# -.net
KiCad netlist of a schematic drawn in Altium Designer
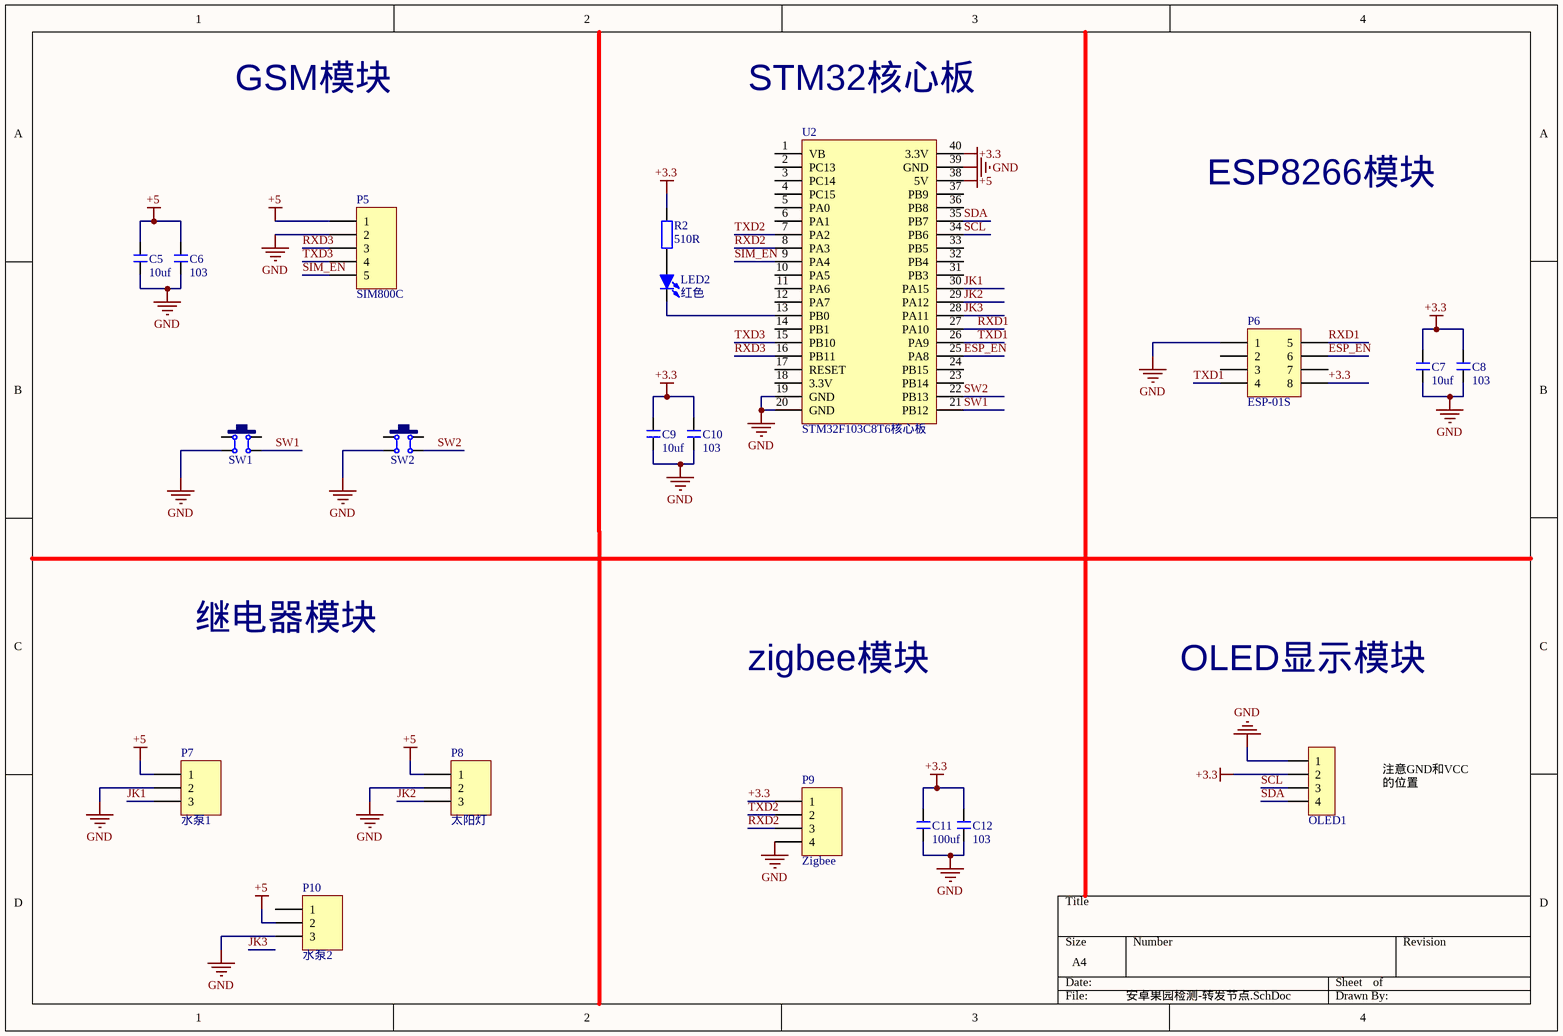
[diagram p0: 安卓果园检测-转发节点.SchDoc]

(export (version "E")
  (design (tool "Eeschema 10.0.6"))
  (components
    (comp (ref "C5")
      (value "10uf")
      (footprint "R 0805_M")
      (description "直插瓷片电容")
      (fields (field (name "版权归属") "源创客"))
      (libsource (lib "3.1   - 电阻-电容-电感") (part "C-CC"))
    )
    (comp (ref "C6")
      (value "103")
      (footprint "R 0805_M")
      (description "直插瓷片电容")
      (fields (field (name "版权归属") "源创客"))
      (libsource (lib "3.1   - 电阻-电容-电感") (part "C-CC"))
    )
    (comp (ref "C7")
      (value "10uf")
      (footprint "R 0805_M")
      (description "直插瓷片电容")
      (fields (field (name "版权归属") "源创客"))
      (libsource (lib "3.1   - 电阻-电容-电感") (part "C-CC"))
    )
    (comp (ref "C8")
      (value "103")
      (footprint "R 0805_M")
      (description "直插瓷片电容")
      (fields (field (name "版权归属") "源创客"))
      (libsource (lib "3.1   - 电阻-电容-电感") (part "C-CC"))
    )
    (comp (ref "C9")
      (value "10uf")
      (footprint "R 0805_M")
      (description "直插瓷片电容")
      (fields (field (name "版权归属") "源创客"))
      (libsource (lib "3.1   - 电阻-电容-电感") (part "C-CC"))
    )
    (comp (ref "C10")
      (value "103")
      (footprint "R 0805_M")
      (description "直插瓷片电容")
      (fields (field (name "版权归属") "源创客"))
      (libsource (lib "3.1   - 电阻-电容-电感") (part "C-CC"))
    )
    (comp (ref "C11")
      (value "100uf")
      (footprint "R 0805_M")
      (description "直插瓷片电容")
      (fields (field (name "版权归属") "源创客"))
      (libsource (lib "3.1   - 电阻-电容-电感") (part "C-CC"))
    )
    (comp (ref "C12")
      (value "103")
      (footprint "R 0805_M")
      (description "直插瓷片电容")
      (fields (field (name "版权归属") "源创客"))
      (libsource (lib "3.1   - 电阻-电容-电感") (part "C-CC"))
    )
    (comp (ref "LED2")
      (value "红色")
      (footprint "LED 0805R")
      (description "贴片LED")
      (fields (field (name "版权归属") "源创客"))
      (libsource (lib "9.1   - LED") (part "LED-SMD"))
    )
    (comp (ref "OLED1")
      (value "HDR-1X4")
      (footprint "HDR2.54-M-LI-4P")
      (description "4P接插件")
      (fields (field (name "版权归属") "源创客"))
      (libsource (lib "4.5   - 接插件-脚距2.54") (part "Header 4"))
    )
    (comp (ref "P5")
      (value "SIM800C")
      (footprint "HDR1X5")
      (description "Header, 5-Pin")
      (fields (field (name "PUBLISHER") "Altium Limited"))
      (libsource (lib "Miscellaneous Connectors") (part "Header 5"))
    )
    (comp (ref "P6")
      (value "ESP-01S")
      (footprint "HDR2X4_CEN")
      (description "Header, 4-Pin, Dual row")
      (fields (field (name "PUBLISHER") "Altium Limited"))
      (libsource (lib "Miscellaneous Connectors") (part "Header 4X2A"))
    )
    (comp (ref "P7")
      (value "水泵1")
      (footprint "MHDR1X3")
      (description "Header, 3-Pin")
      (fields (field (name "PUBLISHER") "Altium Limited"))
      (libsource (lib "Miscellaneous Connectors") (part "MHDR1X3"))
    )
    (comp (ref "P8")
      (value "太阳灯")
      (footprint "MHDR1X3")
      (description "Header, 3-Pin")
      (fields (field (name "PUBLISHER") "Altium Limited"))
      (libsource (lib "Miscellaneous Connectors") (part "MHDR1X3"))
    )
    (comp (ref "P9")
      (value "Zigbee")
      (footprint "HDR1X4")
      (description "Header, 4-Pin")
      (fields (field (name "PUBLISHER") "Altium Limited"))
      (libsource (lib "Miscellaneous Connectors") (part "Header 4"))
    )
    (comp (ref "P10")
      (value "水泵2")
      (footprint "MHDR1X3")
      (description "Header, 3-Pin")
      (fields (field (name "PUBLISHER") "Altium Limited"))
      (libsource (lib "Miscellaneous Connectors") (part "MHDR1X3"))
    )
    (comp (ref "R2")
      (value "510R")
      (footprint "R 0805_M")
      (description "直插色环电阻")
      (fields (field (name "版权归属") "源创客"))
      (libsource (lib "3.1   - 电阻-电容-电感") (part "R-CRR"))
    )
    (comp (ref "SW1")
      (value "6x6x5")
      (footprint "TSW SMD-6*6*4.3")
      (description "贴片6x6轻触开关")
      (fields (field (name "版权归属") "源创客"))
      (libsource (lib "5.1   - 按键-开关") (part "TSW SMD-6x6"))
    )
    (comp (ref "SW2")
      (value "6x6x5")
      (footprint "TSW SMD-6*6*4.3")
      (description "贴片6x6轻触开关")
      (fields (field (name "版权归属") "源创客"))
      (libsource (lib "5.1   - 按键-开关") (part "TSW SMD-6x6"))
    )
    (comp (ref "U2")
      (value "STM32F103C8T6核心板")
      (footprint "DIP40-600_MH")
      (libsource (lib "STM32F103C8T6核心板") (part "STM32F103C8T6核心板"))
    )
  )
  (nets
    (net (code "1") (name "+3.3") (class "Default")
      (node (ref "C10") (pin "1") (pinfunction "1_1") (pintype "passive"))
      (node (ref "C11") (pin "1") (pinfunction "1_1") (pintype "passive"))
      (node (ref "C12") (pin "1") (pinfunction "1_1") (pintype "passive"))
      (node (ref "C7") (pin "1") (pinfunction "1_1") (pintype "passive"))
      (node (ref "C8") (pin "1") (pinfunction "1_1") (pintype "passive"))
      (node (ref "C9") (pin "1") (pinfunction "1_1") (pintype "passive"))
      (node (ref "OLED1") (pin "2") (pinfunction "2_2") (pintype "passive"))
      (node (ref "P6") (pin "8") (pinfunction "8_8") (pintype "passive"))
      (node (ref "P9") (pin "1") (pinfunction "1_1") (pintype "passive"))
      (node (ref "R2") (pin "2") (pinfunction "2_2") (pintype "passive"))
      (node (ref "U2") (pin "40") (pinfunction "3.3V_40") (pintype "passive"))
    )
    (net (code "2") (name "+5") (class "Default")
      (node (ref "C5") (pin "1") (pinfunction "1_1") (pintype "passive"))
      (node (ref "C6") (pin "1") (pinfunction "1_1") (pintype "passive"))
      (node (ref "P10") (pin "2") (pinfunction "2_2") (pintype "passive"))
      (node (ref "P5") (pin "1") (pinfunction "1_1") (pintype "passive"))
      (node (ref "P7") (pin "1") (pinfunction "1_1") (pintype "passive"))
      (node (ref "P8") (pin "1") (pinfunction "1_1") (pintype "passive"))
      (node (ref "U2") (pin "38") (pinfunction "5V_38") (pintype "passive"))
    )
    (net (code "3") (name "/ESP_EN") (class "Default")
      (node (ref "P6") (pin "6") (pinfunction "6_6") (pintype "passive"))
      (node (ref "U2") (pin "25") (pinfunction "PA8_25") (pintype "passive"))
    )
    (net (code "4") (name "/JK1") (class "Default")
      (node (ref "P7") (pin "3") (pinfunction "3_3") (pintype "passive"))
      (node (ref "U2") (pin "30") (pinfunction "PA15_30") (pintype "passive"))
    )
    (net (code "5") (name "/JK2") (class "Default")
      (node (ref "P8") (pin "3") (pinfunction "3_3") (pintype "passive"))
      (node (ref "U2") (pin "29") (pinfunction "PA12_29") (pintype "passive"))
    )
    (net (code "6") (name "/JK3") (class "Default")
      (node (ref "U2") (pin "28") (pinfunction "PA11_28") (pintype "passive"))
    )
    (net (code "7") (name "/RXD1") (class "Default")
      (node (ref "P6") (pin "5") (pinfunction "5_5") (pintype "passive"))
      (node (ref "U2") (pin "27") (pinfunction "PA10_27") (pintype "passive"))
    )
    (net (code "8") (name "/RXD2") (class "Default")
      (node (ref "P9") (pin "3") (pinfunction "3_3") (pintype "passive"))
      (node (ref "U2") (pin "8") (pinfunction "PA3_8") (pintype "passive"))
    )
    (net (code "9") (name "/RXD3") (class "Default")
      (node (ref "P5") (pin "3") (pinfunction "3_3") (pintype "passive"))
      (node (ref "U2") (pin "16") (pinfunction "PB11_16") (pintype "passive"))
    )
    (net (code "10") (name "/SCL") (class "Default")
      (node (ref "OLED1") (pin "3") (pinfunction "3_3") (pintype "passive"))
      (node (ref "U2") (pin "34") (pinfunction "PB6_34") (pintype "passive"))
    )
    (net (code "11") (name "/SDA") (class "Default")
      (node (ref "OLED1") (pin "4") (pinfunction "4_4") (pintype "passive"))
      (node (ref "U2") (pin "35") (pinfunction "PB7_35") (pintype "passive"))
    )
    (net (code "12") (name "/SIM_EN") (class "Default")
      (node (ref "P5") (pin "5") (pinfunction "5_5") (pintype "passive"))
      (node (ref "U2") (pin "9") (pinfunction "PA4_9") (pintype "passive"))
    )
    (net (code "13") (name "/SW1") (class "Default")
      (node (ref "SW1") (pin "3") (pinfunction "3_3") (pintype "passive"))
      (node (ref "U2") (pin "21") (pinfunction "PB12_21") (pintype "passive"))
    )
    (net (code "14") (name "/SW2") (class "Default")
      (node (ref "SW2") (pin "3") (pinfunction "3_3") (pintype "passive"))
      (node (ref "U2") (pin "22") (pinfunction "PB13_22") (pintype "passive"))
    )
    (net (code "15") (name "/TXD1") (class "Default")
      (node (ref "P6") (pin "4") (pinfunction "4_4") (pintype "passive"))
      (node (ref "U2") (pin "26") (pinfunction "PA9_26") (pintype "passive"))
    )
    (net (code "16") (name "/TXD2") (class "Default")
      (node (ref "P9") (pin "2") (pinfunction "2_2") (pintype "passive"))
      (node (ref "U2") (pin "7") (pinfunction "PA2_7") (pintype "passive"))
    )
    (net (code "17") (name "/TXD3") (class "Default")
      (node (ref "P5") (pin "4") (pinfunction "4_4") (pintype "passive"))
      (node (ref "U2") (pin "15") (pinfunction "PB10_15") (pintype "passive"))
    )
    (net (code "18") (name "GND") (class "Default")
      (node (ref "C10") (pin "2") (pinfunction "2_2") (pintype "passive"))
      (node (ref "C11") (pin "2") (pinfunction "2_2") (pintype "passive"))
      (node (ref "C12") (pin "2") (pinfunction "2_2") (pintype "passive"))
      (node (ref "C5") (pin "2") (pinfunction "2_2") (pintype "passive"))
      (node (ref "C6") (pin "2") (pinfunction "2_2") (pintype "passive"))
      (node (ref "C7") (pin "2") (pinfunction "2_2") (pintype "passive"))
      (node (ref "C8") (pin "2") (pinfunction "2_2") (pintype "passive"))
      (node (ref "C9") (pin "2") (pinfunction "2_2") (pintype "passive"))
      (node (ref "OLED1") (pin "1") (pinfunction "1_1") (pintype "passive"))
      (node (ref "P10") (pin "3") (pinfunction "3_3") (pintype "passive"))
      (node (ref "P5") (pin "2") (pinfunction "2_2") (pintype "passive"))
      (node (ref "P6") (pin "1") (pinfunction "1_1") (pintype "passive"))
      (node (ref "P7") (pin "2") (pinfunction "2_2") (pintype "passive"))
      (node (ref "P8") (pin "2") (pinfunction "2_2") (pintype "passive"))
      (node (ref "P9") (pin "4") (pinfunction "4_4") (pintype "passive"))
      (node (ref "SW1") (pin "4") (pinfunction "4_4") (pintype "passive"))
      (node (ref "SW2") (pin "4") (pinfunction "4_4") (pintype "passive"))
      (node (ref "U2") (pin "19") (pinfunction "GND_19") (pintype "passive"))
      (node (ref "U2") (pin "20") (pinfunction "GND_20") (pintype "passive"))
      (node (ref "U2") (pin "39") (pinfunction "GND_39") (pintype "passive"))
    )
    (net (code "19") (name "Net-(LED2-A)") (class "Default")
      (node (ref "LED2") (pin "1") (pinfunction "A_1") (pintype "passive"))
      (node (ref "R2") (pin "1") (pinfunction "1_1") (pintype "passive"))
    )
    (net (code "20") (name "Net-(LED2-K)") (class "Default")
      (node (ref "LED2") (pin "2") (pinfunction "K_2") (pintype "passive"))
      (node (ref "U2") (pin "13") (pinfunction "PB0_13") (pintype "passive"))
    )
    (net (code "21") (name "unconnected-(P6-Pad2)") (class "Default")
      (node (ref "P6") (pin "2") (pinfunction "2_2") (pintype "passive"))
    )
    (net (code "22") (name "unconnected-(P6-Pad3)") (class "Default")
      (node (ref "P6") (pin "3") (pinfunction "3_3") (pintype "passive"))
    )
    (net (code "23") (name "unconnected-(P6-Pad7)") (class "Default")
      (node (ref "P6") (pin "7") (pinfunction "7_7") (pintype "passive"))
    )
    (net (code "24") (name "unconnected-(P10-Pad1)") (class "Default")
      (node (ref "P10") (pin "1") (pinfunction "1_1") (pintype "passive"))
    )
    (net (code "25") (name "unconnected-(SW1-Pad1)") (class "Default")
      (node (ref "SW1") (pin "1") (pinfunction "1_1") (pintype "passive"))
    )
    (net (code "26") (name "unconnected-(SW1-Pad2)") (class "Default")
      (node (ref "SW1") (pin "2") (pinfunction "2_2") (pintype "passive"))
    )
    (net (code "27") (name "unconnected-(SW2-Pad1)") (class "Default")
      (node (ref "SW2") (pin "1") (pinfunction "1_1") (pintype "passive"))
    )
    (net (code "28") (name "unconnected-(SW2-Pad2)") (class "Default")
      (node (ref "SW2") (pin "2") (pinfunction "2_2") (pintype "passive"))
    )
    (net (code "29") (name "unconnected-(U2-3.3V-Pad18)") (class "Default")
      (node (ref "U2") (pin "18") (pinfunction "3.3V_18") (pintype "passive"))
    )
    (net (code "30") (name "unconnected-(U2-PA0-Pad5)") (class "Default")
      (node (ref "U2") (pin "5") (pinfunction "PA0_5") (pintype "passive"))
    )
    (net (code "31") (name "unconnected-(U2-PA1-Pad6)") (class "Default")
      (node (ref "U2") (pin "6") (pinfunction "PA1_6") (pintype "passive"))
    )
    (net (code "32") (name "unconnected-(U2-PA5-Pad10)") (class "Default")
      (node (ref "U2") (pin "10") (pinfunction "PA5_10") (pintype "passive"))
    )
    (net (code "33") (name "unconnected-(U2-PA6-Pad11)") (class "Default")
      (node (ref "U2") (pin "11") (pinfunction "PA6_11") (pintype "passive"))
    )
    (net (code "34") (name "unconnected-(U2-PA7-Pad12)") (class "Default")
      (node (ref "U2") (pin "12") (pinfunction "PA7_12") (pintype "passive"))
    )
    (net (code "35") (name "unconnected-(U2-PB1-Pad14)") (class "Default")
      (node (ref "U2") (pin "14") (pinfunction "PB1_14") (pintype "passive"))
    )
    (net (code "36") (name "unconnected-(U2-PB3-Pad31)") (class "Default")
      (node (ref "U2") (pin "31") (pinfunction "PB3_31") (pintype "passive"))
    )
    (net (code "37") (name "unconnected-(U2-PB4-Pad32)") (class "Default")
      (node (ref "U2") (pin "32") (pinfunction "PB4_32") (pintype "passive"))
    )
    (net (code "38") (name "unconnected-(U2-PB5-Pad33)") (class "Default")
      (node (ref "U2") (pin "33") (pinfunction "PB5_33") (pintype "passive"))
    )
    (net (code "39") (name "unconnected-(U2-PB8-Pad36)") (class "Default")
      (node (ref "U2") (pin "36") (pinfunction "PB8_36") (pintype "passive"))
    )
    (net (code "40") (name "unconnected-(U2-PB9-Pad37)") (class "Default")
      (node (ref "U2") (pin "37") (pinfunction "PB9_37") (pintype "passive"))
    )
    (net (code "41") (name "unconnected-(U2-PB14-Pad23)") (class "Default")
      (node (ref "U2") (pin "23") (pinfunction "PB14_23") (pintype "passive"))
    )
    (net (code "42") (name "unconnected-(U2-PB15-Pad24)") (class "Default")
      (node (ref "U2") (pin "24") (pinfunction "PB15_24") (pintype "passive"))
    )
    (net (code "43") (name "unconnected-(U2-PC13-Pad2)") (class "Default")
      (node (ref "U2") (pin "2") (pinfunction "PC13_2") (pintype "passive"))
    )
    (net (code "44") (name "unconnected-(U2-PC14-Pad3)") (class "Default")
      (node (ref "U2") (pin "3") (pinfunction "PC14_3") (pintype "passive"))
    )
    (net (code "45") (name "unconnected-(U2-PC15-Pad4)") (class "Default")
      (node (ref "U2") (pin "4") (pinfunction "PC15_4") (pintype "passive"))
    )
    (net (code "46") (name "unconnected-(U2-RESET-Pad17)") (class "Default")
      (node (ref "U2") (pin "17") (pinfunction "RESET_17") (pintype "passive"))
    )
    (net (code "47") (name "unconnected-(U2-VB-Pad1)") (class "Default")
      (node (ref "U2") (pin "1") (pinfunction "VB_1") (pintype "passive"))
    )
  )
)
